# RAM.net
KiCad netlist of a schematic drawn in EAGLE
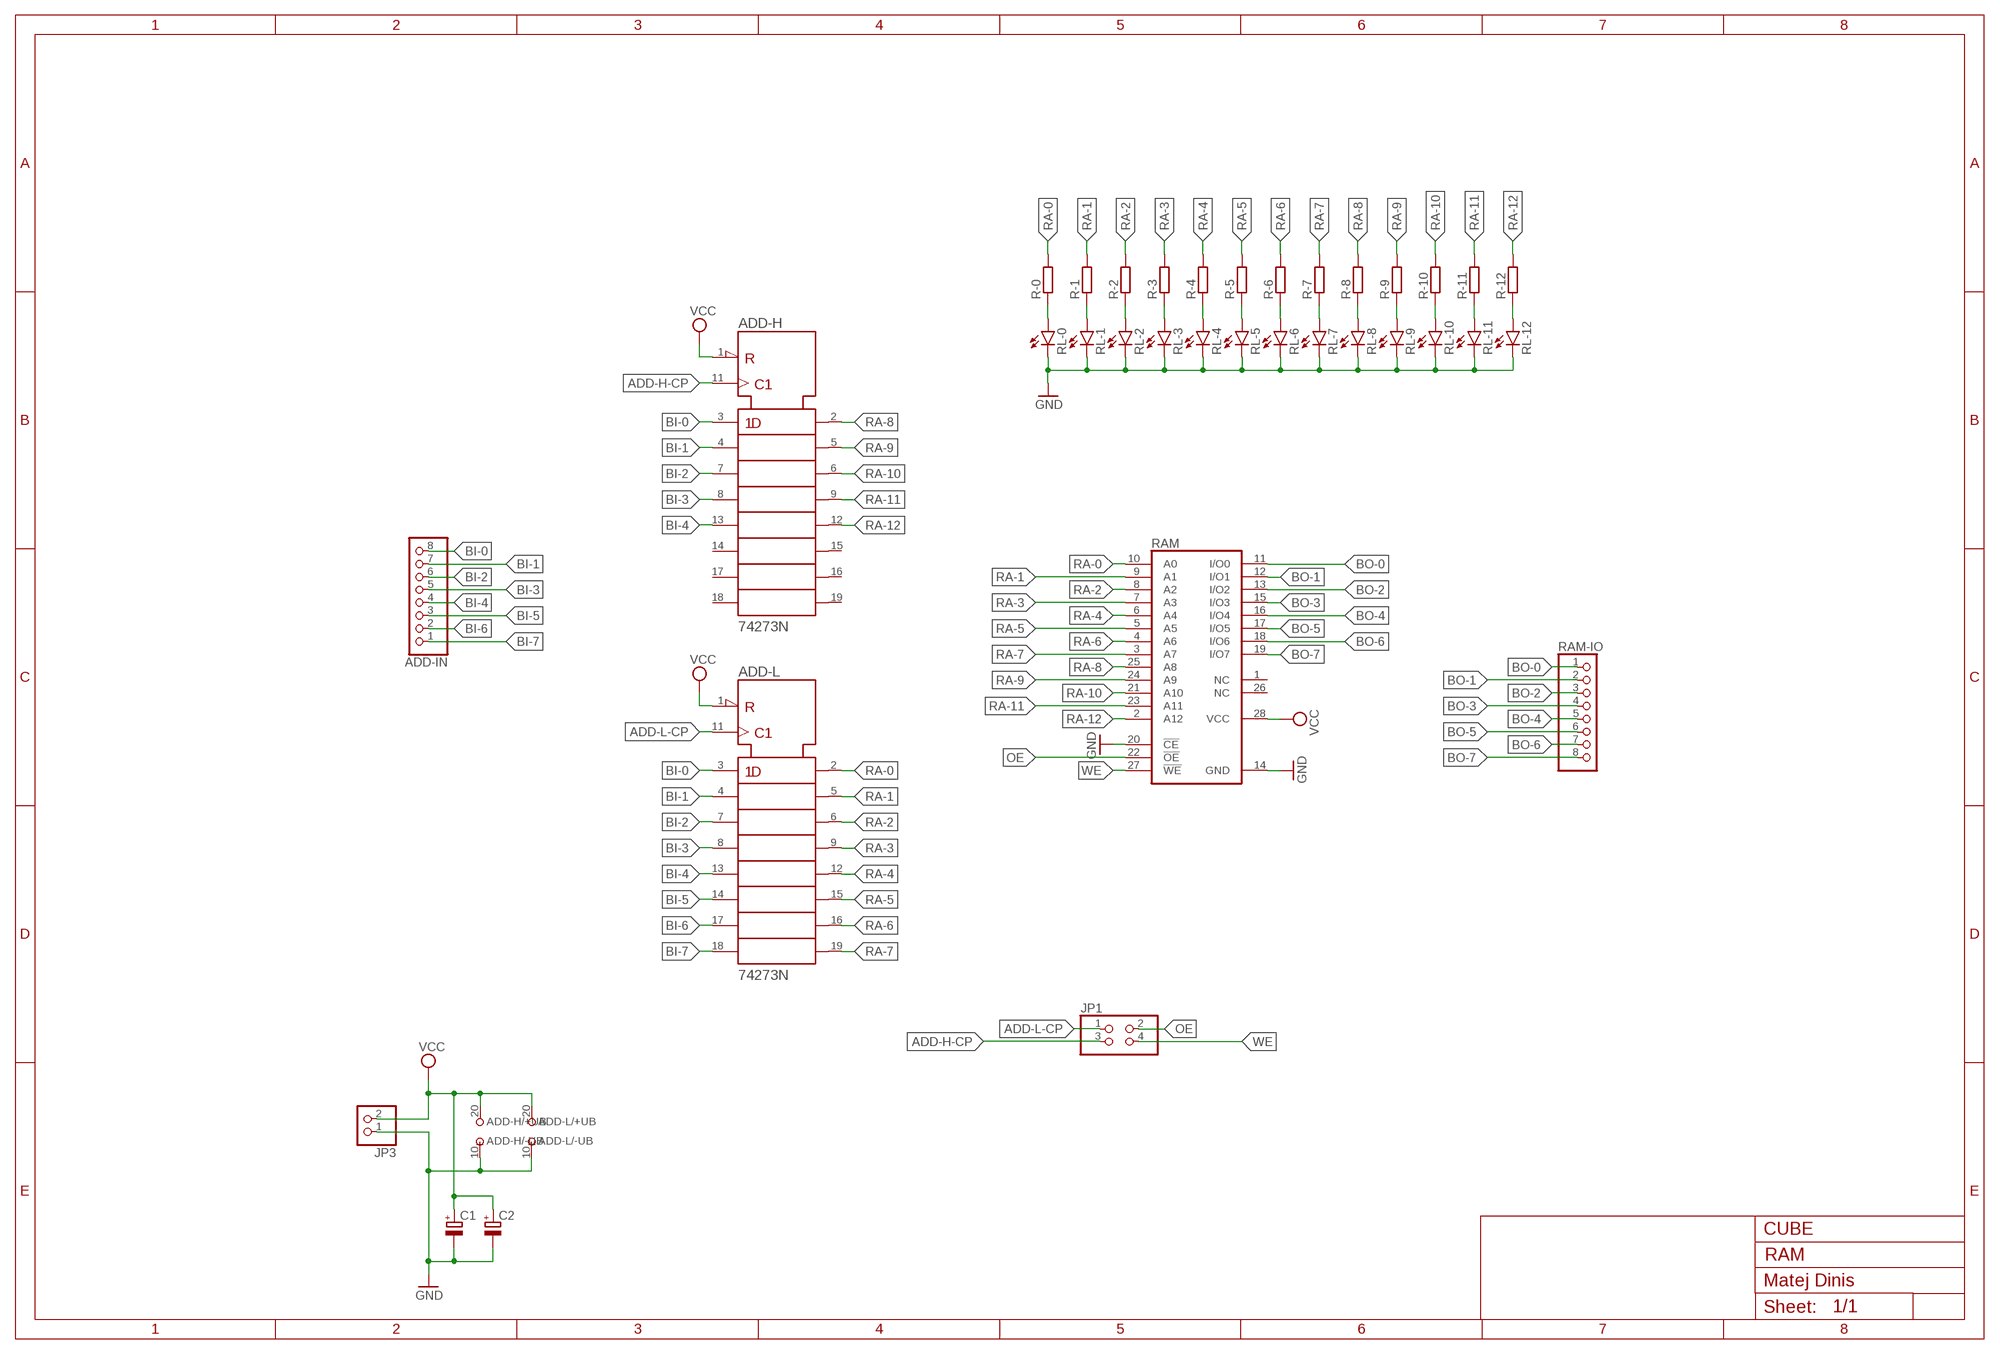
[diagram p0: schematic, sheet 1]

(export (version "E")
  (design (tool "Eeschema 10.0.6"))
  (components
    (comp (ref "ADD-H")
      (value "74273N")
      (footprint "eagle-import:DIL20")
      (libsource (lib "eagle-import") (part "74273N"))
    )
    (comp (ref "ADD-IN")
      (value "PINHD-1X8")
      (footprint "eagle-import:1X08")
      (libsource (lib "eagle-import") (part "PINHD-1X8"))
    )
    (comp (ref "ADD-L")
      (value "74273N")
      (footprint "eagle-import:DIL20")
      (libsource (lib "eagle-import") (part "74273N"))
    )
    (comp (ref "C1")
      (value "CPOL-EUE3.5-8")
      (footprint "eagle-import:E3,5-8")
      (libsource (lib "eagle-import") (part "CPOL-EUE3.5-8"))
    )
    (comp (ref "C2")
      (value "CPOL-EUE3.5-8")
      (footprint "eagle-import:E3,5-8")
      (libsource (lib "eagle-import") (part "CPOL-EUE3.5-8"))
    )
    (comp (ref "JP1")
      (value "PINHD-2X2")
      (footprint "eagle-import:2X02")
      (libsource (lib "eagle-import") (part "PINHD-2X2"))
    )
    (comp (ref "JP3")
      (value "PINHD-1X2")
      (footprint "eagle-import:1X02")
      (libsource (lib "eagle-import") (part "PINHD-1X2"))
    )
    (comp (ref "R-0")
      (value "R-EU_0207/10")
      (footprint "eagle-import:0207_10")
      (libsource (lib "eagle-import") (part "R-EU_0207/10"))
    )
    (comp (ref "R-1")
      (value "R-EU_0207/10")
      (footprint "eagle-import:0207_10")
      (libsource (lib "eagle-import") (part "R-EU_0207/10"))
    )
    (comp (ref "R-2")
      (value "R-EU_0207/10")
      (footprint "eagle-import:0207_10")
      (libsource (lib "eagle-import") (part "R-EU_0207/10"))
    )
    (comp (ref "R-3")
      (value "R-EU_0207/10")
      (footprint "eagle-import:0207_10")
      (libsource (lib "eagle-import") (part "R-EU_0207/10"))
    )
    (comp (ref "R-4")
      (value "R-EU_0207/10")
      (footprint "eagle-import:0207_10")
      (libsource (lib "eagle-import") (part "R-EU_0207/10"))
    )
    (comp (ref "R-5")
      (value "R-EU_0207/10")
      (footprint "eagle-import:0207_10")
      (libsource (lib "eagle-import") (part "R-EU_0207/10"))
    )
    (comp (ref "R-6")
      (value "R-EU_0207/10")
      (footprint "eagle-import:0207_10")
      (libsource (lib "eagle-import") (part "R-EU_0207/10"))
    )
    (comp (ref "R-7")
      (value "R-EU_0207/10")
      (footprint "eagle-import:0207_10")
      (libsource (lib "eagle-import") (part "R-EU_0207/10"))
    )
    (comp (ref "R-8")
      (value "R-EU_0207/10")
      (footprint "eagle-import:0207_10")
      (libsource (lib "eagle-import") (part "R-EU_0207/10"))
    )
    (comp (ref "R-9")
      (value "R-EU_0207/10")
      (footprint "eagle-import:0207_10")
      (libsource (lib "eagle-import") (part "R-EU_0207/10"))
    )
    (comp (ref "R-10")
      (value "R-EU_0207/10")
      (footprint "eagle-import:0207_10")
      (libsource (lib "eagle-import") (part "R-EU_0207/10"))
    )
    (comp (ref "R-11")
      (value "R-EU_0207/10")
      (footprint "eagle-import:0207_10")
      (libsource (lib "eagle-import") (part "R-EU_0207/10"))
    )
    (comp (ref "R-12")
      (value "R-EU_0207/10")
      (footprint "eagle-import:0207_10")
      (libsource (lib "eagle-import") (part "R-EU_0207/10"))
    )
    (comp (ref "RAM")
      (value "28C64C")
      (footprint "eagle-import:DIL28-6")
      (fields (field (name "MPN") "AT28C64B-15PU"))
      (libsource (lib "eagle-import") (part "28C64C"))
    )
    (comp (ref "RAM-IO")
      (value "PINHD-1X8")
      (footprint "eagle-import:1X08")
      (libsource (lib "eagle-import") (part "PINHD-1X8"))
    )
    (comp (ref "RL-0")
      (value "LED5MM")
      (footprint "eagle-import:LED5MM")
      (libsource (lib "eagle-import") (part "LED5MM"))
    )
    (comp (ref "RL-1")
      (value "LED5MM")
      (footprint "eagle-import:LED5MM")
      (libsource (lib "eagle-import") (part "LED5MM"))
    )
    (comp (ref "RL-2")
      (value "LED5MM")
      (footprint "eagle-import:LED5MM")
      (libsource (lib "eagle-import") (part "LED5MM"))
    )
    (comp (ref "RL-3")
      (value "LED5MM")
      (footprint "eagle-import:LED5MM")
      (libsource (lib "eagle-import") (part "LED5MM"))
    )
    (comp (ref "RL-4")
      (value "LED5MM")
      (footprint "eagle-import:LED5MM")
      (libsource (lib "eagle-import") (part "LED5MM"))
    )
    (comp (ref "RL-5")
      (value "LED5MM")
      (footprint "eagle-import:LED5MM")
      (libsource (lib "eagle-import") (part "LED5MM"))
    )
    (comp (ref "RL-6")
      (value "LED5MM")
      (footprint "eagle-import:LED5MM")
      (libsource (lib "eagle-import") (part "LED5MM"))
    )
    (comp (ref "RL-7")
      (value "LED5MM")
      (footprint "eagle-import:LED5MM")
      (libsource (lib "eagle-import") (part "LED5MM"))
    )
    (comp (ref "RL-8")
      (value "LED5MM")
      (footprint "eagle-import:LED5MM")
      (libsource (lib "eagle-import") (part "LED5MM"))
    )
    (comp (ref "RL-9")
      (value "LED5MM")
      (footprint "eagle-import:LED5MM")
      (libsource (lib "eagle-import") (part "LED5MM"))
    )
    (comp (ref "RL-10")
      (value "LED5MM")
      (footprint "eagle-import:LED5MM")
      (libsource (lib "eagle-import") (part "LED5MM"))
    )
    (comp (ref "RL-11")
      (value "LED5MM")
      (footprint "eagle-import:LED5MM")
      (libsource (lib "eagle-import") (part "LED5MM"))
    )
    (comp (ref "RL-12")
      (value "LED5MM")
      (footprint "eagle-import:LED5MM")
      (libsource (lib "eagle-import") (part "LED5MM"))
    )
  )
  (nets
    (net (code "1") (name "ADD-H-CP") (class "Default")
      (node (ref "ADD-H") (pin "11") (pinfunction "CLK_11") (pintype "input"))
      (node (ref "JP1") (pin "3") (pinfunction "3_3") (pintype "passive"))
    )
    (net (code "2") (name "ADD-L-CP") (class "Default")
      (node (ref "ADD-L") (pin "11") (pinfunction "CLK_11") (pintype "input"))
      (node (ref "JP1") (pin "1") (pinfunction "1_1") (pintype "passive"))
    )
    (net (code "3") (name "BI-0") (class "Default")
      (node (ref "ADD-H") (pin "3") (pinfunction "1D_3") (pintype "input"))
      (node (ref "ADD-IN") (pin "8") (pinfunction "8_8") (pintype "passive"))
      (node (ref "ADD-L") (pin "3") (pinfunction "1D_3") (pintype "input"))
    )
    (net (code "4") (name "BI-1") (class "Default")
      (node (ref "ADD-H") (pin "4") (pinfunction "2D_4") (pintype "input"))
      (node (ref "ADD-IN") (pin "7") (pinfunction "7_7") (pintype "passive"))
      (node (ref "ADD-L") (pin "4") (pinfunction "2D_4") (pintype "input"))
    )
    (net (code "5") (name "BI-2") (class "Default")
      (node (ref "ADD-H") (pin "7") (pinfunction "3D_7") (pintype "input"))
      (node (ref "ADD-IN") (pin "6") (pinfunction "6_6") (pintype "passive"))
      (node (ref "ADD-L") (pin "7") (pinfunction "3D_7") (pintype "input"))
    )
    (net (code "6") (name "BI-3") (class "Default")
      (node (ref "ADD-H") (pin "8") (pinfunction "4D_8") (pintype "input"))
      (node (ref "ADD-IN") (pin "5") (pinfunction "5_5") (pintype "passive"))
      (node (ref "ADD-L") (pin "8") (pinfunction "4D_8") (pintype "input"))
    )
    (net (code "7") (name "BI-4") (class "Default")
      (node (ref "ADD-H") (pin "13") (pinfunction "5D_13") (pintype "input"))
      (node (ref "ADD-IN") (pin "4") (pinfunction "4_4") (pintype "passive"))
      (node (ref "ADD-L") (pin "13") (pinfunction "5D_13") (pintype "input"))
    )
    (net (code "8") (name "BI-5") (class "Default")
      (node (ref "ADD-IN") (pin "3") (pinfunction "3_3") (pintype "passive"))
      (node (ref "ADD-L") (pin "14") (pinfunction "6D_14") (pintype "input"))
    )
    (net (code "9") (name "BI-6") (class "Default")
      (node (ref "ADD-IN") (pin "2") (pinfunction "2_2") (pintype "passive"))
      (node (ref "ADD-L") (pin "17") (pinfunction "7D_17") (pintype "input"))
    )
    (net (code "10") (name "BI-7") (class "Default")
      (node (ref "ADD-IN") (pin "1") (pinfunction "1_1") (pintype "passive"))
      (node (ref "ADD-L") (pin "18") (pinfunction "8D_18") (pintype "input"))
    )
    (net (code "11") (name "BO-0") (class "Default")
      (node (ref "RAM") (pin "11") (pinfunction "I/O0_11") (pintype "bidirectional"))
      (node (ref "RAM-IO") (pin "1") (pinfunction "1_1") (pintype "passive"))
    )
    (net (code "12") (name "BO-1") (class "Default")
      (node (ref "RAM") (pin "12") (pinfunction "I/O1_12") (pintype "bidirectional"))
      (node (ref "RAM-IO") (pin "2") (pinfunction "2_2") (pintype "passive"))
    )
    (net (code "13") (name "BO-2") (class "Default")
      (node (ref "RAM") (pin "13") (pinfunction "I/O2_13") (pintype "bidirectional"))
      (node (ref "RAM-IO") (pin "3") (pinfunction "3_3") (pintype "passive"))
    )
    (net (code "14") (name "BO-3") (class "Default")
      (node (ref "RAM") (pin "15") (pinfunction "I/O3_15") (pintype "bidirectional"))
      (node (ref "RAM-IO") (pin "4") (pinfunction "4_4") (pintype "passive"))
    )
    (net (code "15") (name "BO-4") (class "Default")
      (node (ref "RAM") (pin "16") (pinfunction "I/O4_16") (pintype "bidirectional"))
      (node (ref "RAM-IO") (pin "5") (pinfunction "5_5") (pintype "passive"))
    )
    (net (code "16") (name "BO-5") (class "Default")
      (node (ref "RAM") (pin "17") (pinfunction "I/O5_17") (pintype "bidirectional"))
      (node (ref "RAM-IO") (pin "6") (pinfunction "6_6") (pintype "passive"))
    )
    (net (code "17") (name "BO-6") (class "Default")
      (node (ref "RAM") (pin "18") (pinfunction "I/O6_18") (pintype "bidirectional"))
      (node (ref "RAM-IO") (pin "7") (pinfunction "7_7") (pintype "passive"))
    )
    (net (code "18") (name "BO-7") (class "Default")
      (node (ref "RAM") (pin "19") (pinfunction "I/O7_19") (pintype "bidirectional"))
      (node (ref "RAM-IO") (pin "8") (pinfunction "8_8") (pintype "passive"))
    )
    (net (code "19") (name "GND") (class "Default")
      (node (ref "ADD-H") (pin "10") (pinfunction "-UB_10") (pintype "power_in"))
      (node (ref "ADD-L") (pin "10") (pinfunction "-UB_10") (pintype "power_in"))
      (node (ref "C1") (pin "-") (pinfunction "-_-") (pintype "passive"))
      (node (ref "C2") (pin "-") (pinfunction "-_-") (pintype "passive"))
      (node (ref "JP3") (pin "1") (pinfunction "1_1") (pintype "passive"))
      (node (ref "RAM") (pin "14") (pinfunction "GND_14") (pintype "power_in"))
      (node (ref "RAM") (pin "20") (pinfunction "~{CE}_20") (pintype "input"))
      (node (ref "RL-0") (pin "K") (pinfunction "C_K") (pintype "passive"))
      (node (ref "RL-1") (pin "K") (pinfunction "C_K") (pintype "passive"))
      (node (ref "RL-10") (pin "K") (pinfunction "C_K") (pintype "passive"))
      (node (ref "RL-11") (pin "K") (pinfunction "C_K") (pintype "passive"))
      (node (ref "RL-12") (pin "K") (pinfunction "C_K") (pintype "passive"))
      (node (ref "RL-2") (pin "K") (pinfunction "C_K") (pintype "passive"))
      (node (ref "RL-3") (pin "K") (pinfunction "C_K") (pintype "passive"))
      (node (ref "RL-4") (pin "K") (pinfunction "C_K") (pintype "passive"))
      (node (ref "RL-5") (pin "K") (pinfunction "C_K") (pintype "passive"))
      (node (ref "RL-6") (pin "K") (pinfunction "C_K") (pintype "passive"))
      (node (ref "RL-7") (pin "K") (pinfunction "C_K") (pintype "passive"))
      (node (ref "RL-8") (pin "K") (pinfunction "C_K") (pintype "passive"))
      (node (ref "RL-9") (pin "K") (pinfunction "C_K") (pintype "passive"))
    )
    (net (code "20") (name "Net-(R-0-Pad1)") (class "Default")
      (node (ref "R-0") (pin "1") (pinfunction "1_1") (pintype "passive"))
      (node (ref "RL-0") (pin "A") (pinfunction "A_A") (pintype "passive"))
    )
    (net (code "21") (name "Net-(R-1-Pad1)") (class "Default")
      (node (ref "R-1") (pin "1") (pinfunction "1_1") (pintype "passive"))
      (node (ref "RL-1") (pin "A") (pinfunction "A_A") (pintype "passive"))
    )
    (net (code "22") (name "Net-(R-2-Pad1)") (class "Default")
      (node (ref "R-2") (pin "1") (pinfunction "1_1") (pintype "passive"))
      (node (ref "RL-2") (pin "A") (pinfunction "A_A") (pintype "passive"))
    )
    (net (code "23") (name "Net-(R-3-Pad1)") (class "Default")
      (node (ref "R-3") (pin "1") (pinfunction "1_1") (pintype "passive"))
      (node (ref "RL-3") (pin "A") (pinfunction "A_A") (pintype "passive"))
    )
    (net (code "24") (name "Net-(R-4-Pad1)") (class "Default")
      (node (ref "R-4") (pin "1") (pinfunction "1_1") (pintype "passive"))
      (node (ref "RL-4") (pin "A") (pinfunction "A_A") (pintype "passive"))
    )
    (net (code "25") (name "Net-(R-5-Pad1)") (class "Default")
      (node (ref "R-5") (pin "1") (pinfunction "1_1") (pintype "passive"))
      (node (ref "RL-5") (pin "A") (pinfunction "A_A") (pintype "passive"))
    )
    (net (code "26") (name "Net-(R-6-Pad1)") (class "Default")
      (node (ref "R-6") (pin "1") (pinfunction "1_1") (pintype "passive"))
      (node (ref "RL-6") (pin "A") (pinfunction "A_A") (pintype "passive"))
    )
    (net (code "27") (name "Net-(R-7-Pad1)") (class "Default")
      (node (ref "R-7") (pin "1") (pinfunction "1_1") (pintype "passive"))
      (node (ref "RL-7") (pin "A") (pinfunction "A_A") (pintype "passive"))
    )
    (net (code "28") (name "Net-(R-8-Pad1)") (class "Default")
      (node (ref "R-8") (pin "1") (pinfunction "1_1") (pintype "passive"))
      (node (ref "RL-8") (pin "A") (pinfunction "A_A") (pintype "passive"))
    )
    (net (code "29") (name "Net-(R-9-Pad1)") (class "Default")
      (node (ref "R-9") (pin "1") (pinfunction "1_1") (pintype "passive"))
      (node (ref "RL-9") (pin "A") (pinfunction "A_A") (pintype "passive"))
    )
    (net (code "30") (name "Net-(R-10-Pad1)") (class "Default")
      (node (ref "R-10") (pin "1") (pinfunction "1_1") (pintype "passive"))
      (node (ref "RL-10") (pin "A") (pinfunction "A_A") (pintype "passive"))
    )
    (net (code "31") (name "Net-(R-11-Pad1)") (class "Default")
      (node (ref "R-11") (pin "1") (pinfunction "1_1") (pintype "passive"))
      (node (ref "RL-11") (pin "A") (pinfunction "A_A") (pintype "passive"))
    )
    (net (code "32") (name "Net-(R-12-Pad1)") (class "Default")
      (node (ref "R-12") (pin "1") (pinfunction "1_1") (pintype "passive"))
      (node (ref "RL-12") (pin "A") (pinfunction "A_A") (pintype "passive"))
    )
    (net (code "33") (name "OE") (class "Default")
      (node (ref "JP1") (pin "2") (pinfunction "2_2") (pintype "passive"))
      (node (ref "RAM") (pin "22") (pinfunction "~{OE}_22") (pintype "input"))
    )
    (net (code "34") (name "RA-0") (class "Default")
      (node (ref "ADD-L") (pin "2") (pinfunction "1Q_2") (pintype "output"))
      (node (ref "R-0") (pin "2") (pinfunction "2_2") (pintype "passive"))
      (node (ref "RAM") (pin "10") (pinfunction "A0_10") (pintype "input"))
    )
    (net (code "35") (name "RA-1") (class "Default")
      (node (ref "ADD-L") (pin "5") (pinfunction "2Q_5") (pintype "output"))
      (node (ref "R-1") (pin "2") (pinfunction "2_2") (pintype "passive"))
      (node (ref "RAM") (pin "9") (pinfunction "A1_9") (pintype "input"))
    )
    (net (code "36") (name "RA-2") (class "Default")
      (node (ref "ADD-L") (pin "6") (pinfunction "3Q_6") (pintype "output"))
      (node (ref "R-2") (pin "2") (pinfunction "2_2") (pintype "passive"))
      (node (ref "RAM") (pin "8") (pinfunction "A2_8") (pintype "input"))
    )
    (net (code "37") (name "RA-3") (class "Default")
      (node (ref "ADD-L") (pin "9") (pinfunction "4Q_9") (pintype "output"))
      (node (ref "R-3") (pin "2") (pinfunction "2_2") (pintype "passive"))
      (node (ref "RAM") (pin "7") (pinfunction "A3_7") (pintype "input"))
    )
    (net (code "38") (name "RA-4") (class "Default")
      (node (ref "ADD-L") (pin "12") (pinfunction "5Q_12") (pintype "output"))
      (node (ref "R-4") (pin "2") (pinfunction "2_2") (pintype "passive"))
      (node (ref "RAM") (pin "6") (pinfunction "A4_6") (pintype "input"))
    )
    (net (code "39") (name "RA-5") (class "Default")
      (node (ref "ADD-L") (pin "15") (pinfunction "6Q_15") (pintype "output"))
      (node (ref "R-5") (pin "2") (pinfunction "2_2") (pintype "passive"))
      (node (ref "RAM") (pin "5") (pinfunction "A5_5") (pintype "input"))
    )
    (net (code "40") (name "RA-6") (class "Default")
      (node (ref "ADD-L") (pin "16") (pinfunction "7Q_16") (pintype "output"))
      (node (ref "R-6") (pin "2") (pinfunction "2_2") (pintype "passive"))
      (node (ref "RAM") (pin "4") (pinfunction "A6_4") (pintype "input"))
    )
    (net (code "41") (name "RA-7") (class "Default")
      (node (ref "ADD-L") (pin "19") (pinfunction "8Q_19") (pintype "output"))
      (node (ref "R-7") (pin "2") (pinfunction "2_2") (pintype "passive"))
      (node (ref "RAM") (pin "3") (pinfunction "A7_3") (pintype "input"))
    )
    (net (code "42") (name "RA-8") (class "Default")
      (node (ref "ADD-H") (pin "2") (pinfunction "1Q_2") (pintype "output"))
      (node (ref "R-8") (pin "2") (pinfunction "2_2") (pintype "passive"))
      (node (ref "RAM") (pin "25") (pinfunction "A8_25") (pintype "input"))
    )
    (net (code "43") (name "RA-9") (class "Default")
      (node (ref "ADD-H") (pin "5") (pinfunction "2Q_5") (pintype "output"))
      (node (ref "R-9") (pin "2") (pinfunction "2_2") (pintype "passive"))
      (node (ref "RAM") (pin "24") (pinfunction "A9_24") (pintype "input"))
    )
    (net (code "44") (name "RA-10") (class "Default")
      (node (ref "ADD-H") (pin "6") (pinfunction "3Q_6") (pintype "output"))
      (node (ref "R-10") (pin "2") (pinfunction "2_2") (pintype "passive"))
      (node (ref "RAM") (pin "21") (pinfunction "A10_21") (pintype "input"))
    )
    (net (code "45") (name "RA-11") (class "Default")
      (node (ref "ADD-H") (pin "9") (pinfunction "4Q_9") (pintype "output"))
      (node (ref "R-11") (pin "2") (pinfunction "2_2") (pintype "passive"))
      (node (ref "RAM") (pin "23") (pinfunction "A11_23") (pintype "input"))
    )
    (net (code "46") (name "RA-12") (class "Default")
      (node (ref "ADD-H") (pin "12") (pinfunction "5Q_12") (pintype "output"))
      (node (ref "R-12") (pin "2") (pinfunction "2_2") (pintype "passive"))
      (node (ref "RAM") (pin "2") (pinfunction "A12_2") (pintype "input"))
    )
    (net (code "47") (name "VCC") (class "Default")
      (node (ref "ADD-H") (pin "1") (pinfunction "~{CLR}_1") (pintype "input"))
      (node (ref "ADD-H") (pin "20") (pinfunction "+UB_20") (pintype "power_in"))
      (node (ref "ADD-L") (pin "1") (pinfunction "~{CLR}_1") (pintype "input"))
      (node (ref "ADD-L") (pin "20") (pinfunction "+UB_20") (pintype "power_in"))
      (node (ref "C1") (pin "+") (pinfunction "+_+") (pintype "passive"))
      (node (ref "C2") (pin "+") (pinfunction "+_+") (pintype "passive"))
      (node (ref "JP3") (pin "2") (pinfunction "2_2") (pintype "passive"))
      (node (ref "RAM") (pin "28") (pinfunction "VCC_28") (pintype "power_in"))
    )
    (net (code "48") (name "WE") (class "Default")
      (node (ref "JP1") (pin "4") (pinfunction "4_4") (pintype "passive"))
      (node (ref "RAM") (pin "27") (pinfunction "~{WE}_27") (pintype "input"))
    )
    (net (code "49") (name "unconnected-(ADD-HC-6D-Pad14)") (class "Default")
      (node (ref "ADD-H") (pin "14") (pinfunction "6D_14") (pintype "input"))
    )
    (net (code "50") (name "unconnected-(ADD-HC-6Q-Pad15)") (class "Default")
      (node (ref "ADD-H") (pin "15") (pinfunction "6Q_15") (pintype "output"))
    )
    (net (code "51") (name "unconnected-(ADD-HC-7D-Pad17)") (class "Default")
      (node (ref "ADD-H") (pin "17") (pinfunction "7D_17") (pintype "input"))
    )
    (net (code "52") (name "unconnected-(ADD-HC-7Q-Pad16)") (class "Default")
      (node (ref "ADD-H") (pin "16") (pinfunction "7Q_16") (pintype "output"))
    )
    (net (code "53") (name "unconnected-(ADD-HC-8D-Pad18)") (class "Default")
      (node (ref "ADD-H") (pin "18") (pinfunction "8D_18") (pintype "input"))
    )
    (net (code "54") (name "unconnected-(ADD-HC-8Q-Pad19)") (class "Default")
      (node (ref "ADD-H") (pin "19") (pinfunction "8Q_19") (pintype "output"))
    )
    (net (code "55") (name "unconnected-(RAM-NC-Pad1)") (class "Default")
      (node (ref "RAM") (pin "1") (pinfunction "NC_1") (pintype "no_connect"))
    )
    (net (code "56") (name "unconnected-(RAM-NC-Pad26)") (class "Default")
      (node (ref "RAM") (pin "26") (pinfunction "NC_26") (pintype "no_connect"))
    )
  )
)
